# switch-amp.net
KiCad netlist of a schematic drawn in EAGLE
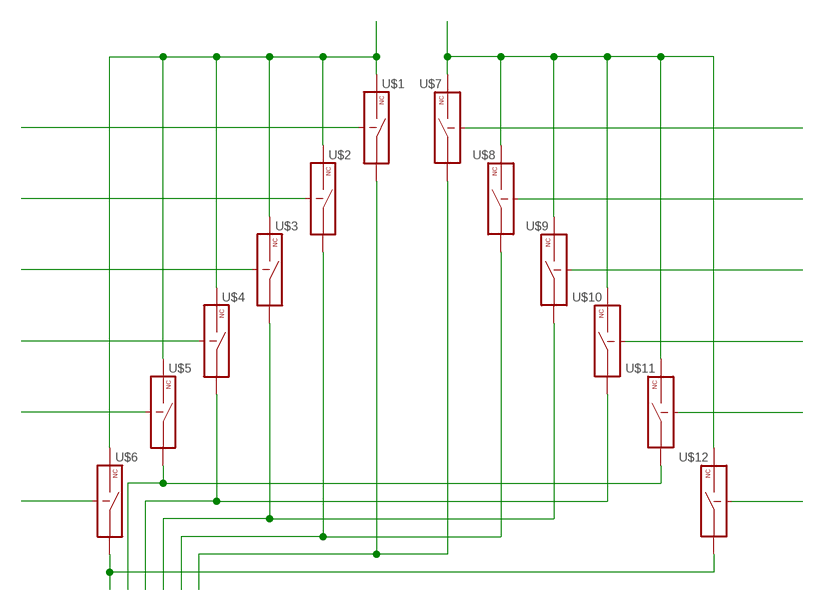
[diagram p0: schematic, sheet 1]

(export (version "E")
  (design (tool "Eeschema 10.0.6"))
  (components
    (comp (ref "U$1")
      (value "DG467")
      (footprint "eagle-import:TSSOP-6")
      (libsource (lib "eagle-import") (part "DG467"))
    )
    (comp (ref "U$2")
      (value "DG467")
      (footprint "eagle-import:TSSOP-6")
      (libsource (lib "eagle-import") (part "DG467"))
    )
    (comp (ref "U$3")
      (value "DG467")
      (footprint "eagle-import:TSSOP-6")
      (libsource (lib "eagle-import") (part "DG467"))
    )
    (comp (ref "U$4")
      (value "DG467")
      (footprint "eagle-import:TSSOP-6")
      (libsource (lib "eagle-import") (part "DG467"))
    )
    (comp (ref "U$5")
      (value "DG467")
      (footprint "eagle-import:TSSOP-6")
      (libsource (lib "eagle-import") (part "DG467"))
    )
    (comp (ref "U$6")
      (value "DG467")
      (footprint "eagle-import:TSSOP-6")
      (libsource (lib "eagle-import") (part "DG467"))
    )
    (comp (ref "U$7")
      (value "DG467")
      (footprint "eagle-import:TSSOP-6")
      (libsource (lib "eagle-import") (part "DG467"))
    )
    (comp (ref "U$8")
      (value "DG467")
      (footprint "eagle-import:TSSOP-6")
      (libsource (lib "eagle-import") (part "DG467"))
    )
    (comp (ref "U$9")
      (value "DG467")
      (footprint "eagle-import:TSSOP-6")
      (libsource (lib "eagle-import") (part "DG467"))
    )
    (comp (ref "U$10")
      (value "DG467")
      (footprint "eagle-import:TSSOP-6")
      (libsource (lib "eagle-import") (part "DG467"))
    )
    (comp (ref "U$11")
      (value "DG467")
      (footprint "eagle-import:TSSOP-6")
      (libsource (lib "eagle-import") (part "DG467"))
    )
    (comp (ref "U$12")
      (value "DG467")
      (footprint "eagle-import:TSSOP-6")
      (libsource (lib "eagle-import") (part "DG467"))
    )
  )
  (nets
    (net (code "1") (name "Net-(U$1A-COM)") (class "Default")
      (node (ref "U$1") (pin "P$6") (pinfunction "COM_P$6") (pintype "bidirectional"))
      (node (ref "U$7") (pin "P$6") (pinfunction "COM_P$6") (pintype "bidirectional"))
    )
    (net (code "2") (name "Net-(U$1A-IN)") (class "Default")
      (node (ref "U$1") (pin "P$1") (pinfunction "IN_P$1") (pintype "bidirectional"))
      (node (ref "U$2") (pin "P$1") (pinfunction "IN_P$1") (pintype "bidirectional"))
      (node (ref "U$3") (pin "P$1") (pinfunction "IN_P$1") (pintype "bidirectional"))
      (node (ref "U$4") (pin "P$1") (pinfunction "IN_P$1") (pintype "bidirectional"))
      (node (ref "U$5") (pin "P$1") (pinfunction "IN_P$1") (pintype "bidirectional"))
      (node (ref "U$6") (pin "P$1") (pinfunction "IN_P$1") (pintype "bidirectional"))
    )
    (net (code "3") (name "Net-(U$2A-COM)") (class "Default")
      (node (ref "U$2") (pin "P$6") (pinfunction "COM_P$6") (pintype "bidirectional"))
      (node (ref "U$8") (pin "P$6") (pinfunction "COM_P$6") (pintype "bidirectional"))
    )
    (net (code "4") (name "Net-(U$3A-COM)") (class "Default")
      (node (ref "U$3") (pin "P$6") (pinfunction "COM_P$6") (pintype "bidirectional"))
      (node (ref "U$9") (pin "P$6") (pinfunction "COM_P$6") (pintype "bidirectional"))
    )
    (net (code "5") (name "Net-(U$10A-COM)") (class "Default")
      (node (ref "U$10") (pin "P$6") (pinfunction "COM_P$6") (pintype "bidirectional"))
      (node (ref "U$4") (pin "P$6") (pinfunction "COM_P$6") (pintype "bidirectional"))
    )
    (net (code "6") (name "Net-(U$10A-IN)") (class "Default")
      (node (ref "U$10") (pin "P$1") (pinfunction "IN_P$1") (pintype "bidirectional"))
      (node (ref "U$11") (pin "P$1") (pinfunction "IN_P$1") (pintype "bidirectional"))
      (node (ref "U$12") (pin "P$1") (pinfunction "IN_P$1") (pintype "bidirectional"))
      (node (ref "U$7") (pin "P$1") (pinfunction "IN_P$1") (pintype "bidirectional"))
      (node (ref "U$8") (pin "P$1") (pinfunction "IN_P$1") (pintype "bidirectional"))
      (node (ref "U$9") (pin "P$1") (pinfunction "IN_P$1") (pintype "bidirectional"))
    )
    (net (code "7") (name "Net-(U$11A-COM)") (class "Default")
      (node (ref "U$11") (pin "P$6") (pinfunction "COM_P$6") (pintype "bidirectional"))
      (node (ref "U$5") (pin "P$6") (pinfunction "COM_P$6") (pintype "bidirectional"))
    )
    (net (code "8") (name "Net-(U$12A-COM)") (class "Default")
      (node (ref "U$12") (pin "P$6") (pinfunction "COM_P$6") (pintype "bidirectional"))
      (node (ref "U$6") (pin "P$6") (pinfunction "COM_P$6") (pintype "bidirectional"))
    )
    (net (code "9") (name "unconnected-(U$1A-CTL-PadP$3)") (class "Default")
      (node (ref "U$1") (pin "P$3") (pinfunction "CTL_P$3") (pintype "bidirectional"))
    )
    (net (code "10") (name "unconnected-(U$2A-CTL-PadP$3)") (class "Default")
      (node (ref "U$2") (pin "P$3") (pinfunction "CTL_P$3") (pintype "bidirectional"))
    )
    (net (code "11") (name "unconnected-(U$3A-CTL-PadP$3)") (class "Default")
      (node (ref "U$3") (pin "P$3") (pinfunction "CTL_P$3") (pintype "bidirectional"))
    )
    (net (code "12") (name "unconnected-(U$4A-CTL-PadP$3)") (class "Default")
      (node (ref "U$4") (pin "P$3") (pinfunction "CTL_P$3") (pintype "bidirectional"))
    )
    (net (code "13") (name "unconnected-(U$5A-CTL-PadP$3)") (class "Default")
      (node (ref "U$5") (pin "P$3") (pinfunction "CTL_P$3") (pintype "bidirectional"))
    )
    (net (code "14") (name "unconnected-(U$6A-CTL-PadP$3)") (class "Default")
      (node (ref "U$6") (pin "P$3") (pinfunction "CTL_P$3") (pintype "bidirectional"))
    )
    (net (code "15") (name "unconnected-(U$7A-CTL-PadP$3)") (class "Default")
      (node (ref "U$7") (pin "P$3") (pinfunction "CTL_P$3") (pintype "bidirectional"))
    )
    (net (code "16") (name "unconnected-(U$8A-CTL-PadP$3)") (class "Default")
      (node (ref "U$8") (pin "P$3") (pinfunction "CTL_P$3") (pintype "bidirectional"))
    )
    (net (code "17") (name "unconnected-(U$9A-CTL-PadP$3)") (class "Default")
      (node (ref "U$9") (pin "P$3") (pinfunction "CTL_P$3") (pintype "bidirectional"))
    )
    (net (code "18") (name "unconnected-(U$10A-CTL-PadP$3)") (class "Default")
      (node (ref "U$10") (pin "P$3") (pinfunction "CTL_P$3") (pintype "bidirectional"))
    )
    (net (code "19") (name "unconnected-(U$11A-CTL-PadP$3)") (class "Default")
      (node (ref "U$11") (pin "P$3") (pinfunction "CTL_P$3") (pintype "bidirectional"))
    )
    (net (code "20") (name "unconnected-(U$12A-CTL-PadP$3)") (class "Default")
      (node (ref "U$12") (pin "P$3") (pinfunction "CTL_P$3") (pintype "bidirectional"))
    )
  )
)
